# 5__HDMI.net
KiCad netlist of a schematic drawn in Altium Designer
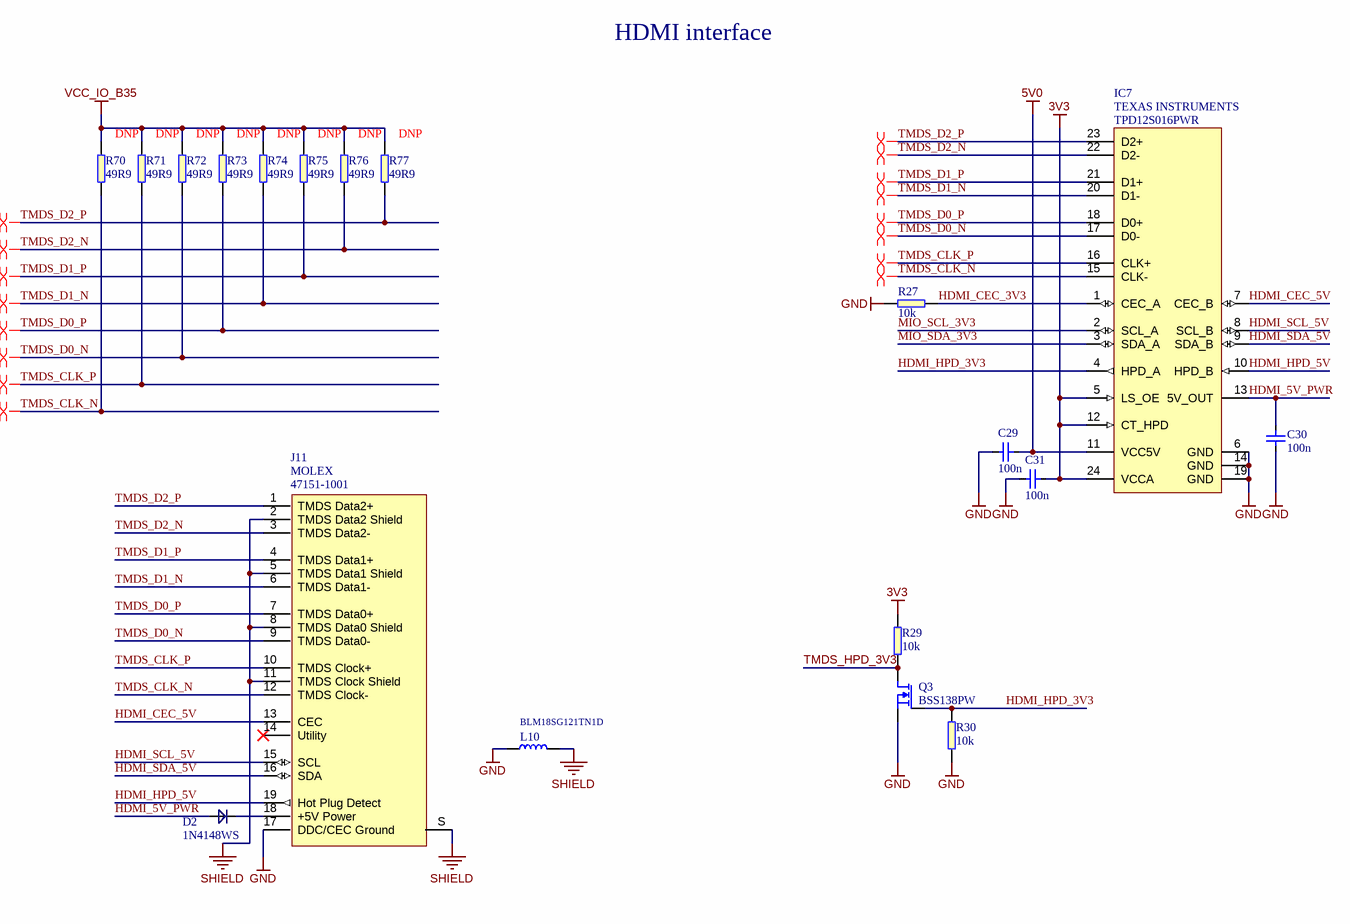
[diagram p0: [5]_HDMI.SchDoc]

(export (version "E")
  (design (tool "Eeschema 10.0.6"))
  (components
    (comp (ref "C29")
      (value "100n")
      (footprint "0402")
      (description "MLCC SMT Capacitor 100nF 0402")
      (fields (field (name "PART NUMBER") "C_100n_0402") (field (name "VOLTAGE") "10V"))
      (libsource (lib "Zynq-Video-Board-Rev-1.2") (part "C_100n_0402"))
    )
    (comp (ref "C30")
      (value "100n")
      (footprint "0402")
      (description "MLCC SMT Capacitor 100nF 0402")
      (fields (field (name "PART NUMBER") "C_100n_0402") (field (name "VOLTAGE") "10V"))
      (libsource (lib "Zynq-Video-Board-Rev-1.2") (part "C_100n_0402"))
    )
    (comp (ref "C31")
      (value "100n")
      (footprint "0402")
      (description "MLCC SMT Capacitor 100nF 0402")
      (fields (field (name "PART NUMBER") "C_100n_0402") (field (name "VOLTAGE") "10V"))
      (libsource (lib "Zynq-Video-Board-Rev-1.2") (part "C_100n_0402"))
    )
    (comp (ref "D2")
      (value "1N4148WS")
      (footprint "SOD-323")
      (description "Diode small signal")
      (fields (field (name "MANUFACTURER") "ON SEMICONDUCTOR"))
      (libsource (lib "Zynq-Video-Board-Rev-1.2") (part "1N4148WS"))
    )
    (comp (ref "IC7")
      (value "TPD12S016PWR")
      (footprint "TSOP65P640X120-24L")
      (description "TPD12S016PWR is a single-chip High Definition Multimedia Interface (HDMI)")
      (fields (field (name "MANUFACTURER") "TEXAS INSTRUMENTS"))
      (libsource (lib "Zynq-Video-Board-Rev-1.2") (part "TPD12S016PWR"))
    )
    (comp (ref "J11")
      (value "47151-1001")
      (footprint "Molex_HDMI_471511001")
      (description "Header right angle HDMI")
      (fields (field (name "PART NUMBER") "CON-Molex-471511001") (field (name "MANUFACTURER") "MOLEX"))
      (libsource (lib "Zynq-Video-Board-Rev-1.2") (part "CON-Molex-471511001"))
    )
    (comp (ref "L10")
      (value "BLM18SG121TN1D")
      (footprint "0603")
      (description "FERRITE BEAD, 0.025OHM, 3A, 0603")
      (fields (field (name "MANUFACTURER") "MURATA"))
      (libsource (lib "Zynq-Video-Board-Rev-1.2") (part "BLM18SG121TN1D"))
    )
    (comp (ref "Q3")
      (value "BSS138PW")
      (footprint "SC70-3")
      (description "MOSFET, N CH, 60V, 0.2A")
      (fields (field (name "MANUFACTURER") "NXP"))
      (libsource (lib "Zynq-Video-Board-Rev-1.2") (part "NMOS"))
    )
    (comp (ref "R27")
      (value "10k")
      (footprint "0402")
      (description "SMT Resistor 10k 0402")
      (fields (field (name "PART NUMBER") "R_10k_0402") (field (name "TOLERANCE") "1%"))
      (libsource (lib "") (part "R_10k_0402_1"))
    )
    (comp (ref "R29")
      (value "10k")
      (footprint "0402")
      (description "SMT Resistor 10k 0402")
      (fields (field (name "PART NUMBER") "R_10k_0402") (field (name "TOLERANCE") "1%"))
      (libsource (lib "Zynq-Video-Board-Rev-1.2") (part "R_10k_0402"))
    )
    (comp (ref "R30")
      (value "10k")
      (footprint "0402")
      (description "SMT Resistor 10k 0402")
      (fields (field (name "PART NUMBER") "R_10k_0402") (field (name "TOLERANCE") "1%"))
      (libsource (lib "Zynq-Video-Board-Rev-1.2") (part "R_10k_0402"))
    )
    (comp (ref "R70")
      (value "49R9")
      (footprint "0402")
      (description "SMT Resistor 49R9 0402")
      (fields (field (name "PART NUMBER") "R_49R9_0402") (field (name "TOLERANCE") "1%"))
      (libsource (lib "Zynq-Video-Board-Rev-1.2") (part "R_49R9_0402"))
    )
    (comp (ref "R71")
      (value "49R9")
      (footprint "0402")
      (description "SMT Resistor 49R9 0402")
      (fields (field (name "PART NUMBER") "R_49R9_0402") (field (name "TOLERANCE") "1%"))
      (libsource (lib "Zynq-Video-Board-Rev-1.2") (part "R_49R9_0402"))
    )
    (comp (ref "R72")
      (value "49R9")
      (footprint "0402")
      (description "SMT Resistor 49R9 0402")
      (fields (field (name "PART NUMBER") "R_49R9_0402") (field (name "TOLERANCE") "1%"))
      (libsource (lib "Zynq-Video-Board-Rev-1.2") (part "R_49R9_0402"))
    )
    (comp (ref "R73")
      (value "49R9")
      (footprint "0402")
      (description "SMT Resistor 49R9 0402")
      (fields (field (name "PART NUMBER") "R_49R9_0402") (field (name "TOLERANCE") "1%"))
      (libsource (lib "Zynq-Video-Board-Rev-1.2") (part "R_49R9_0402"))
    )
    (comp (ref "R74")
      (value "49R9")
      (footprint "0402")
      (description "SMT Resistor 49R9 0402")
      (fields (field (name "PART NUMBER") "R_49R9_0402") (field (name "TOLERANCE") "1%"))
      (libsource (lib "Zynq-Video-Board-Rev-1.2") (part "R_49R9_0402"))
    )
    (comp (ref "R75")
      (value "49R9")
      (footprint "0402")
      (description "SMT Resistor 49R9 0402")
      (fields (field (name "PART NUMBER") "R_49R9_0402") (field (name "TOLERANCE") "1%"))
      (libsource (lib "Zynq-Video-Board-Rev-1.2") (part "R_49R9_0402"))
    )
    (comp (ref "R76")
      (value "49R9")
      (footprint "0402")
      (description "SMT Resistor 49R9 0402")
      (fields (field (name "PART NUMBER") "R_49R9_0402") (field (name "TOLERANCE") "1%"))
      (libsource (lib "Zynq-Video-Board-Rev-1.2") (part "R_49R9_0402"))
    )
    (comp (ref "R77")
      (value "49R9")
      (footprint "0402")
      (description "SMT Resistor 49R9 0402")
      (fields (field (name "PART NUMBER") "R_49R9_0402") (field (name "TOLERANCE") "1%"))
      (libsource (lib "Zynq-Video-Board-Rev-1.2") (part "R_49R9_0402"))
    )
  )
  (nets
    (net (code "1") (name "/HDMI_5V_PWR") (class "Default")
      (node (ref "C30") (pin "1") (pinfunction "1_1") (pintype "passive"))
      (node (ref "D2") (pin "A") (pinfunction "A_A") (pintype "passive"))
      (node (ref "IC7") (pin "13") (pinfunction "5V_OUT_13") (pintype "power_in"))
    )
    (net (code "2") (name "/HDMI_CEC_3V3") (class "Default")
      (node (ref "IC7") (pin "1") (pinfunction "CEC_A_1") (pintype "bidirectional"))
      (node (ref "R27") (pin "2") (pintype "passive"))
    )
    (net (code "3") (name "/HDMI_CEC_5V") (class "Default")
      (node (ref "IC7") (pin "7") (pinfunction "CEC_B_7") (pintype "bidirectional"))
      (node (ref "J11") (pin "13") (pinfunction "CEC_13") (pintype "passive"))
    )
    (net (code "4") (name "/HDMI_HPD_3V3") (class "Default")
      (node (ref "IC7") (pin "4") (pinfunction "HPD_A_4") (pintype "output"))
      (node (ref "Q3") (pin "1") (pinfunction "G_1") (pintype "passive"))
      (node (ref "R30") (pin "2") (pintype "passive"))
    )
    (net (code "5") (name "/HDMI_HPD_5V") (class "Default")
      (node (ref "IC7") (pin "10") (pinfunction "HPD_B_10") (pintype "input"))
      (node (ref "J11") (pin "19") (pinfunction "Hot_Plug_Detect_19") (pintype "output"))
    )
    (net (code "6") (name "/HDMI_SCL_5V") (class "Default")
      (node (ref "IC7") (pin "8") (pinfunction "SCL_B_8") (pintype "bidirectional"))
      (node (ref "J11") (pin "15") (pinfunction "SCL_15") (pintype "bidirectional"))
    )
    (net (code "7") (name "/HDMI_SDA_5V") (class "Default")
      (node (ref "IC7") (pin "9") (pinfunction "SDA_B_9") (pintype "bidirectional"))
      (node (ref "J11") (pin "16") (pinfunction "SDA_16") (pintype "bidirectional"))
    )
    (net (code "8") (name "/MIO_SCL_3V3") (class "Default")
      (node (ref "IC7") (pin "2") (pinfunction "SCL_A_2") (pintype "bidirectional"))
    )
    (net (code "9") (name "/MIO_SDA_3V3") (class "Default")
      (node (ref "IC7") (pin "3") (pinfunction "SDA_A_3") (pintype "bidirectional"))
    )
    (net (code "10") (name "/TMDS_CLK_N") (class "Default")
      (node (ref "IC7") (pin "15") (pinfunction "CLK-_15") (pintype "passive"))
      (node (ref "J11") (pin "12") (pinfunction "TMDS_Clock-_12") (pintype "passive"))
      (node (ref "R70") (pin "1") (pintype "passive"))
    )
    (net (code "11") (name "/TMDS_CLK_P") (class "Default")
      (node (ref "IC7") (pin "16") (pinfunction "CLK+_16") (pintype "passive"))
      (node (ref "J11") (pin "10") (pinfunction "TMDS_Clock+_10") (pintype "passive"))
      (node (ref "R71") (pin "1") (pintype "passive"))
    )
    (net (code "12") (name "/TMDS_D0_N") (class "Default")
      (node (ref "IC7") (pin "17") (pinfunction "D0-_17") (pintype "passive"))
      (node (ref "J11") (pin "9") (pinfunction "TMDS_Data0-_9") (pintype "passive"))
      (node (ref "R72") (pin "1") (pintype "passive"))
    )
    (net (code "13") (name "/TMDS_D0_P") (class "Default")
      (node (ref "IC7") (pin "18") (pinfunction "D0+_18") (pintype "passive"))
      (node (ref "J11") (pin "7") (pinfunction "TMDS_Data0+_7") (pintype "passive"))
      (node (ref "R73") (pin "1") (pintype "passive"))
    )
    (net (code "14") (name "/TMDS_D1_N") (class "Default")
      (node (ref "IC7") (pin "20") (pinfunction "D1-_20") (pintype "passive"))
      (node (ref "J11") (pin "6") (pinfunction "TMDS_Data1-_6") (pintype "passive"))
      (node (ref "R74") (pin "1") (pintype "passive"))
    )
    (net (code "15") (name "/TMDS_D1_P") (class "Default")
      (node (ref "IC7") (pin "21") (pinfunction "D1+_21") (pintype "passive"))
      (node (ref "J11") (pin "4") (pinfunction "TMDS_Data1+_4") (pintype "passive"))
      (node (ref "R75") (pin "1") (pintype "passive"))
    )
    (net (code "16") (name "/TMDS_D2_N") (class "Default")
      (node (ref "IC7") (pin "22") (pinfunction "D2-_22") (pintype "passive"))
      (node (ref "J11") (pin "3") (pinfunction "TMDS_Data2-_3") (pintype "passive"))
      (node (ref "R76") (pin "1") (pintype "passive"))
    )
    (net (code "17") (name "/TMDS_D2_P") (class "Default")
      (node (ref "IC7") (pin "23") (pinfunction "D2+_23") (pintype "passive"))
      (node (ref "J11") (pin "1") (pinfunction "TMDS_Data2+_1") (pintype "passive"))
      (node (ref "R77") (pin "1") (pintype "passive"))
    )
    (net (code "18") (name "/TMDS_HPD_3V3") (class "Default")
      (node (ref "Q3") (pin "3") (pinfunction "D_3") (pintype "passive"))
      (node (ref "R29") (pin "1") (pintype "passive"))
    )
    (net (code "19") (name "3V3") (class "Default")
      (node (ref "C31") (pin "1") (pinfunction "1_1") (pintype "passive"))
      (node (ref "IC7") (pin "12") (pinfunction "CT_HPD_12") (pintype "input"))
      (node (ref "IC7") (pin "24") (pinfunction "VCCA_24") (pintype "power_in"))
      (node (ref "IC7") (pin "5") (pinfunction "LS_OE_5") (pintype "input"))
      (node (ref "R29") (pin "2") (pintype "passive"))
    )
    (net (code "20") (name "5V0") (class "Default")
      (node (ref "C29") (pin "1") (pinfunction "1_1") (pintype "passive"))
      (node (ref "IC7") (pin "11") (pinfunction "VCC5V_11") (pintype "power_in"))
    )
    (net (code "21") (name "GND") (class "Default")
      (node (ref "C29") (pin "2") (pinfunction "2_2") (pintype "passive"))
      (node (ref "C30") (pin "2") (pinfunction "2_2") (pintype "passive"))
      (node (ref "C31") (pin "2") (pinfunction "2_2") (pintype "passive"))
      (node (ref "IC7") (pin "14") (pinfunction "GND_14") (pintype "power_in"))
      (node (ref "IC7") (pin "19") (pinfunction "GND_19") (pintype "power_in"))
      (node (ref "IC7") (pin "6") (pinfunction "GND_6") (pintype "power_in"))
      (node (ref "J11") (pin "17") (pinfunction "DDC/CEC_Ground_17") (pintype "power_in"))
      (node (ref "L10") (pin "1") (pintype "passive"))
      (node (ref "Q3") (pin "2") (pinfunction "S_2") (pintype "passive"))
      (node (ref "R27") (pin "1") (pintype "passive"))
      (node (ref "R30") (pin "1") (pintype "passive"))
    )
    (net (code "22") (name "Net-(J11-+5V_Power)") (class "Default")
      (node (ref "D2") (pin "C") (pinfunction "C_C") (pintype "passive"))
      (node (ref "J11") (pin "18") (pinfunction "+5V_Power_18") (pintype "power_in"))
    )
    (net (code "23") (name "SHIELD") (class "Default")
      (node (ref "J11") (pin "11") (pinfunction "TMDS_Clock_Shield_11") (pintype "passive"))
      (node (ref "J11") (pin "2") (pinfunction "TMDS_Data2_Shield_2") (pintype "passive"))
      (node (ref "J11") (pin "5") (pinfunction "TMDS_Data1_Shield_5") (pintype "passive"))
      (node (ref "J11") (pin "8") (pinfunction "TMDS_Data0_Shield_8") (pintype "passive"))
      (node (ref "J11") (pin "S") (pinfunction "SH_S") (pintype "passive"))
      (node (ref "L10") (pin "2") (pintype "passive"))
    )
    (net (code "24") (name "VCC_IO_B35") (class "Default")
      (node (ref "R70") (pin "2") (pintype "passive"))
      (node (ref "R71") (pin "2") (pintype "passive"))
      (node (ref "R72") (pin "2") (pintype "passive"))
      (node (ref "R73") (pin "2") (pintype "passive"))
      (node (ref "R74") (pin "2") (pintype "passive"))
      (node (ref "R75") (pin "2") (pintype "passive"))
      (node (ref "R76") (pin "2") (pintype "passive"))
      (node (ref "R77") (pin "2") (pintype "passive"))
    )
    (net (code "25") (name "unconnected-(J11-Utility-Pad14)") (class "Default")
      (node (ref "J11") (pin "14") (pinfunction "Utility_14") (pintype "passive+no_connect"))
    )
  )
)
